# BHONoff.net
KiCad netlist of a schematic drawn in EAGLE
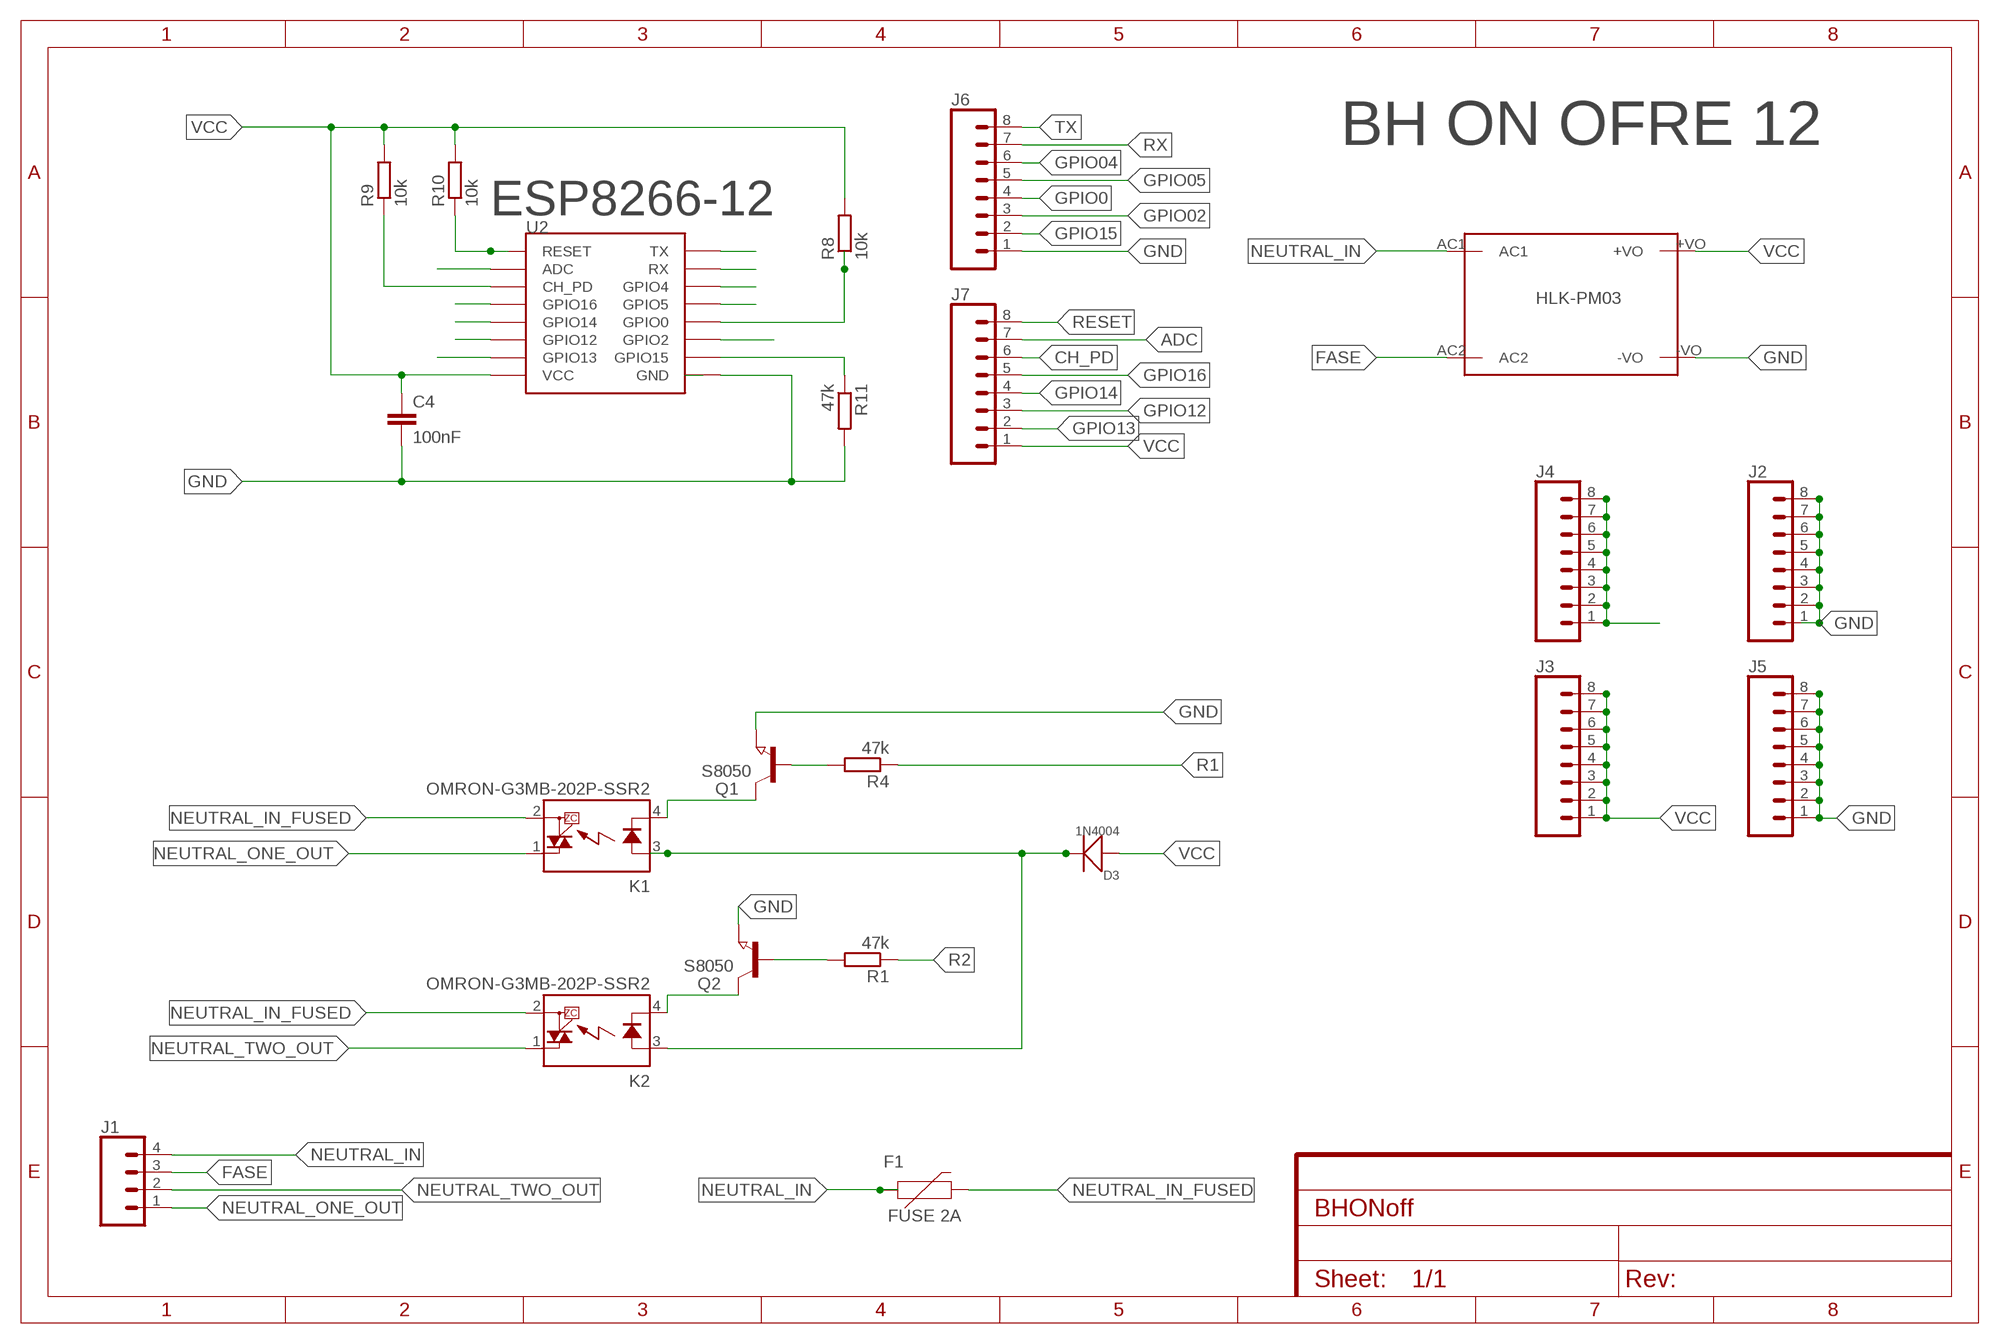
[diagram p0: schematic, sheet 1]

(export (version "E")
  (design (tool "Eeschema 10.0.6"))
  (components
    (comp (ref "C4")
      (value "100nF")
      (footprint "eagle-import:0603")
      (libsource (lib "eagle-import") (part "10NF-0603-50V-10%"))
    )
    (comp (ref "D3")
      (value "1N4004")
      (footprint "eagle-import:DO-214AC")
      (fields (field (name "MPN") "1N4007"))
      (libsource (lib "eagle-import") (part "DIODE-GEN-PURPOSE-1KV-1A(DO-214AC)"))
    )
    (comp (ref "F1")
      (value "FUSE 2A")
      (footprint "eagle-import:PTH")
      (libsource (lib "eagle-import") (part "PPTC_PTH"))
    )
    (comp (ref "J1")
      (value "CONN_04SCREW")
      (footprint "eagle-import:SCREWTERMINAL-3.5MM-4")
      (libsource (lib "eagle-import") (part "CONN_04SCREW"))
    )
    (comp (ref "J2")
      (value "CONN_08\"")
      (footprint "eagle-import:1X08")
      (libsource (lib "eagle-import") (part "CONN_08{dblquote}"))
    )
    (comp (ref "J3")
      (value "CONN_08\"")
      (footprint "eagle-import:1X08")
      (libsource (lib "eagle-import") (part "CONN_08{dblquote}"))
    )
    (comp (ref "J4")
      (value "CONN_08\"")
      (footprint "eagle-import:1X08")
      (libsource (lib "eagle-import") (part "CONN_08{dblquote}"))
    )
    (comp (ref "J5")
      (value "CONN_08\"")
      (footprint "eagle-import:1X08")
      (libsource (lib "eagle-import") (part "CONN_08{dblquote}"))
    )
    (comp (ref "J6")
      (value "CONN_08\"")
      (footprint "eagle-import:1X08")
      (libsource (lib "eagle-import") (part "CONN_08{dblquote}"))
    )
    (comp (ref "J7")
      (value "CONN_08\"")
      (footprint "eagle-import:1X08")
      (libsource (lib "eagle-import") (part "CONN_08{dblquote}"))
    )
    (comp (ref "K1")
      (value "OMRON-G3MB-202P-SSR2")
      (footprint "eagle-import:OMRON-G3MB-202P-SSR")
      (fields (field (name "MPN") "S202S02F"))
      (libsource (lib "eagle-import") (part "OMRON-G3MB-202P-SSR2"))
    )
    (comp (ref "K2")
      (value "OMRON-G3MB-202P-SSR2")
      (footprint "eagle-import:OMRON-G3MB-202P-SSR")
      (fields (field (name "MPN") "S202S02F"))
      (libsource (lib "eagle-import") (part "OMRON-G3MB-202P-SSR2"))
    )
    (comp (ref "Q1")
      (value "S8050")
      (footprint "eagle-import:SOT23")
      (libsource (lib "eagle-import") (part "NPN-TRANSISTOR_SOT23"))
    )
    (comp (ref "Q2")
      (value "S8050")
      (footprint "eagle-import:SOT23")
      (libsource (lib "eagle-import") (part "NPN-TRANSISTOR_SOT23"))
    )
    (comp (ref "R1")
      (value "47k")
      (footprint "eagle-import:R0603")
      (libsource (lib "eagle-import") (part "R-EU_R0603"))
    )
    (comp (ref "R4")
      (value "47k")
      (footprint "eagle-import:R0603")
      (libsource (lib "eagle-import") (part "R-EU_R0603"))
    )
    (comp (ref "R8")
      (value "10k")
      (footprint "eagle-import:R0603")
      (libsource (lib "eagle-import") (part "R-EU_R0603"))
    )
    (comp (ref "R9")
      (value "10k")
      (footprint "eagle-import:R0603")
      (libsource (lib "eagle-import") (part "R-EU_R0603"))
    )
    (comp (ref "R10")
      (value "10k")
      (footprint "eagle-import:R0603")
      (libsource (lib "eagle-import") (part "R-EU_R0603"))
    )
    (comp (ref "R11")
      (value "47k")
      (footprint "eagle-import:R0603")
      (libsource (lib "eagle-import") (part "R-EU_R0603"))
    )
    (comp (ref "U$2")
      (value "HLK-PM03")
      (footprint "eagle-import:HLK-PM03")
      (libsource (lib "eagle-import") (part "HLK-PM03"))
    )
    (comp (ref "U2")
      (value "ESP12SMD")
      (footprint "eagle-import:ESP12-SMD")
      (libsource (lib "eagle-import") (part "ESP12SMD"))
    )
  )
  (nets
    (net (code "1") (name "ADC") (class "Default")
      (node (ref "J7") (pin "7") (pinfunction "7_7") (pintype "passive"))
      (node (ref "U2") (pin "ADC") (pinfunction "ADC_ADC") (pintype "bidirectional"))
    )
    (net (code "2") (name "CH_PD") (class "Default")
      (node (ref "J7") (pin "6") (pinfunction "6_6") (pintype "passive"))
      (node (ref "R9") (pin "1") (pinfunction "1_1") (pintype "passive"))
      (node (ref "U2") (pin "CH_PD") (pinfunction "CH_PD_CH_PD") (pintype "bidirectional"))
    )
    (net (code "3") (name "FASE") (class "Default")
      (node (ref "J1") (pin "3") (pinfunction "3_3") (pintype "passive"))
      (node (ref "U$2") (pin "AC2") (pinfunction "AC2_AC2") (pintype "bidirectional"))
    )
    (net (code "4") (name "GND") (class "Default")
      (node (ref "C4") (pin "2") (pinfunction "2_2") (pintype "passive"))
      (node (ref "J2") (pin "1") (pinfunction "1_1") (pintype "passive"))
      (node (ref "J2") (pin "2") (pinfunction "2_2") (pintype "passive"))
      (node (ref "J2") (pin "3") (pinfunction "3_3") (pintype "passive"))
      (node (ref "J2") (pin "4") (pinfunction "4_4") (pintype "passive"))
      (node (ref "J2") (pin "5") (pinfunction "5_5") (pintype "passive"))
      (node (ref "J2") (pin "6") (pinfunction "6_6") (pintype "passive"))
      (node (ref "J2") (pin "7") (pinfunction "7_7") (pintype "passive"))
      (node (ref "J2") (pin "8") (pinfunction "8_8") (pintype "passive"))
      (node (ref "J5") (pin "1") (pinfunction "1_1") (pintype "passive"))
      (node (ref "J5") (pin "2") (pinfunction "2_2") (pintype "passive"))
      (node (ref "J5") (pin "3") (pinfunction "3_3") (pintype "passive"))
      (node (ref "J5") (pin "4") (pinfunction "4_4") (pintype "passive"))
      (node (ref "J5") (pin "5") (pinfunction "5_5") (pintype "passive"))
      (node (ref "J5") (pin "6") (pinfunction "6_6") (pintype "passive"))
      (node (ref "J5") (pin "7") (pinfunction "7_7") (pintype "passive"))
      (node (ref "J5") (pin "8") (pinfunction "8_8") (pintype "passive"))
      (node (ref "J6") (pin "1") (pinfunction "1_1") (pintype "passive"))
      (node (ref "Q1") (pin "2") (pinfunction "E_2") (pintype "passive"))
      (node (ref "Q2") (pin "2") (pinfunction "E_2") (pintype "passive"))
      (node (ref "R11") (pin "2") (pinfunction "2_2") (pintype "passive"))
      (node (ref "U$2") (pin "-VO") (pinfunction "-VO_-VO") (pintype "bidirectional"))
      (node (ref "U2") (pin "GND") (pinfunction "GND_GND") (pintype "bidirectional"))
    )
    (net (code "5") (name "GPIO0") (class "Default")
      (node (ref "J6") (pin "4") (pinfunction "4_4") (pintype "passive"))
      (node (ref "R8") (pin "1") (pinfunction "1_1") (pintype "passive"))
      (node (ref "U2") (pin "GPIO0") (pinfunction "GPIO0_GPIO0") (pintype "bidirectional"))
    )
    (net (code "6") (name "GPIO02") (class "Default")
      (node (ref "J6") (pin "3") (pinfunction "3_3") (pintype "passive"))
      (node (ref "U2") (pin "GPIO2") (pinfunction "GPIO2_GPIO2") (pintype "bidirectional"))
    )
    (net (code "7") (name "GPIO04") (class "Default")
      (node (ref "J6") (pin "6") (pinfunction "6_6") (pintype "passive"))
      (node (ref "U2") (pin "GPIO4") (pinfunction "GPIO4_GPIO4") (pintype "bidirectional"))
    )
    (net (code "8") (name "GPIO05") (class "Default")
      (node (ref "J6") (pin "5") (pinfunction "5_5") (pintype "passive"))
      (node (ref "U2") (pin "GPIO5") (pinfunction "GPIO5_GPIO5") (pintype "bidirectional"))
    )
    (net (code "9") (name "GPIO12") (class "Default")
      (node (ref "J7") (pin "3") (pinfunction "3_3") (pintype "passive"))
      (node (ref "U2") (pin "GPIO12") (pinfunction "GPIO12_GPIO12") (pintype "bidirectional"))
    )
    (net (code "10") (name "GPIO13") (class "Default")
      (node (ref "J7") (pin "2") (pinfunction "2_2") (pintype "passive"))
      (node (ref "U2") (pin "GPIO13") (pinfunction "GPIO13_GPIO13") (pintype "bidirectional"))
    )
    (net (code "11") (name "GPIO14") (class "Default")
      (node (ref "J7") (pin "4") (pinfunction "4_4") (pintype "passive"))
      (node (ref "U2") (pin "GPIO14") (pinfunction "GPIO14_GPIO14") (pintype "bidirectional"))
    )
    (net (code "12") (name "GPIO15") (class "Default")
      (node (ref "J6") (pin "2") (pinfunction "2_2") (pintype "passive"))
      (node (ref "R11") (pin "1") (pinfunction "1_1") (pintype "passive"))
      (node (ref "U2") (pin "GPIO15") (pinfunction "GPIO15_GPIO15") (pintype "bidirectional"))
    )
    (net (code "13") (name "GPIO16") (class "Default")
      (node (ref "J7") (pin "5") (pinfunction "5_5") (pintype "passive"))
      (node (ref "U2") (pin "GPIO16") (pinfunction "GPIO16_GPIO16") (pintype "bidirectional"))
    )
    (net (code "14") (name "NEUTRAL_IN") (class "Default")
      (node (ref "F1") (pin "P$1") (pinfunction "1_P$1") (pintype "bidirectional"))
      (node (ref "J1") (pin "4") (pinfunction "4_4") (pintype "passive"))
      (node (ref "U$2") (pin "AC1") (pinfunction "AC1_AC1") (pintype "bidirectional"))
    )
    (net (code "15") (name "NEUTRAL_IN_FUSED") (class "Default")
      (node (ref "F1") (pin "P$2") (pinfunction "2_P$2") (pintype "bidirectional"))
      (node (ref "K1") (pin "2") (pinfunction "DS2_2") (pintype "passive"))
      (node (ref "K2") (pin "2") (pinfunction "DS2_2") (pintype "passive"))
    )
    (net (code "16") (name "NEUTRAL_ONE_OUT") (class "Default")
      (node (ref "J1") (pin "1") (pinfunction "1_1") (pintype "passive"))
      (node (ref "K1") (pin "1") (pinfunction "DS1_1") (pintype "passive"))
    )
    (net (code "17") (name "NEUTRAL_TWO_OUT") (class "Default")
      (node (ref "J1") (pin "2") (pinfunction "2_2") (pintype "passive"))
      (node (ref "K2") (pin "1") (pinfunction "DS1_1") (pintype "passive"))
    )
    (net (code "18") (name "Net-(D3--)") (class "Default")
      (node (ref "D3") (pin "2") (pinfunction "-_2") (pintype "passive"))
      (node (ref "K1") (pin "3") (pinfunction "A_3") (pintype "passive"))
      (node (ref "K2") (pin "3") (pinfunction "A_3") (pintype "passive"))
    )
    (net (code "19") (name "Net-(K1-K)") (class "Default")
      (node (ref "K1") (pin "4") (pinfunction "K_4") (pintype "passive"))
      (node (ref "Q1") (pin "3") (pinfunction "C_3") (pintype "passive"))
    )
    (net (code "20") (name "Net-(K2-K)") (class "Default")
      (node (ref "K2") (pin "4") (pinfunction "K_4") (pintype "passive"))
      (node (ref "Q2") (pin "3") (pinfunction "C_3") (pintype "passive"))
    )
    (net (code "21") (name "Net-(Q1-B)") (class "Default")
      (node (ref "Q1") (pin "1") (pinfunction "B_1") (pintype "passive"))
      (node (ref "R4") (pin "2") (pinfunction "2_2") (pintype "passive"))
    )
    (net (code "22") (name "Net-(Q2-B)") (class "Default")
      (node (ref "Q2") (pin "1") (pinfunction "B_1") (pintype "passive"))
      (node (ref "R1") (pin "2") (pinfunction "2_2") (pintype "passive"))
    )
    (net (code "23") (name "R1") (class "Default")
      (node (ref "R4") (pin "1") (pinfunction "1_1") (pintype "passive"))
    )
    (net (code "24") (name "R2") (class "Default")
      (node (ref "R1") (pin "1") (pinfunction "1_1") (pintype "passive"))
    )
    (net (code "25") (name "RESET") (class "Default")
      (node (ref "J7") (pin "8") (pinfunction "8_8") (pintype "passive"))
      (node (ref "R10") (pin "1") (pinfunction "1_1") (pintype "passive"))
      (node (ref "U2") (pin "RESET") (pinfunction "RESET_RESET") (pintype "bidirectional"))
    )
    (net (code "26") (name "RX") (class "Default")
      (node (ref "J6") (pin "7") (pinfunction "7_7") (pintype "passive"))
      (node (ref "U2") (pin "RXD0") (pinfunction "RX_RXD0") (pintype "bidirectional"))
    )
    (net (code "27") (name "TX") (class "Default")
      (node (ref "J6") (pin "8") (pinfunction "8_8") (pintype "passive"))
      (node (ref "U2") (pin "TXD0") (pinfunction "TX_TXD0") (pintype "bidirectional"))
    )
    (net (code "28") (name "VCC") (class "Default")
      (node (ref "C4") (pin "1") (pinfunction "1_1") (pintype "passive"))
      (node (ref "D3") (pin "1") (pinfunction "+_1") (pintype "passive"))
      (node (ref "J3") (pin "1") (pinfunction "1_1") (pintype "passive"))
      (node (ref "J3") (pin "2") (pinfunction "2_2") (pintype "passive"))
      (node (ref "J3") (pin "3") (pinfunction "3_3") (pintype "passive"))
      (node (ref "J3") (pin "4") (pinfunction "4_4") (pintype "passive"))
      (node (ref "J3") (pin "5") (pinfunction "5_5") (pintype "passive"))
      (node (ref "J3") (pin "6") (pinfunction "6_6") (pintype "passive"))
      (node (ref "J3") (pin "7") (pinfunction "7_7") (pintype "passive"))
      (node (ref "J3") (pin "8") (pinfunction "8_8") (pintype "passive"))
      (node (ref "J4") (pin "1") (pinfunction "1_1") (pintype "passive"))
      (node (ref "J4") (pin "2") (pinfunction "2_2") (pintype "passive"))
      (node (ref "J4") (pin "3") (pinfunction "3_3") (pintype "passive"))
      (node (ref "J4") (pin "4") (pinfunction "4_4") (pintype "passive"))
      (node (ref "J4") (pin "5") (pinfunction "5_5") (pintype "passive"))
      (node (ref "J4") (pin "6") (pinfunction "6_6") (pintype "passive"))
      (node (ref "J4") (pin "7") (pinfunction "7_7") (pintype "passive"))
      (node (ref "J4") (pin "8") (pinfunction "8_8") (pintype "passive"))
      (node (ref "J7") (pin "1") (pinfunction "1_1") (pintype "passive"))
      (node (ref "R10") (pin "2") (pinfunction "2_2") (pintype "passive"))
      (node (ref "R8") (pin "2") (pinfunction "2_2") (pintype "passive"))
      (node (ref "R9") (pin "2") (pinfunction "2_2") (pintype "passive"))
      (node (ref "U$2") (pin "+VO") (pinfunction "+VO_+VO") (pintype "bidirectional"))
      (node (ref "U2") (pin "VCC") (pinfunction "VCC_VCC") (pintype "bidirectional"))
    )
  )
)
